# design.net
KiCad netlist of a schematic drawn in Altium Designer
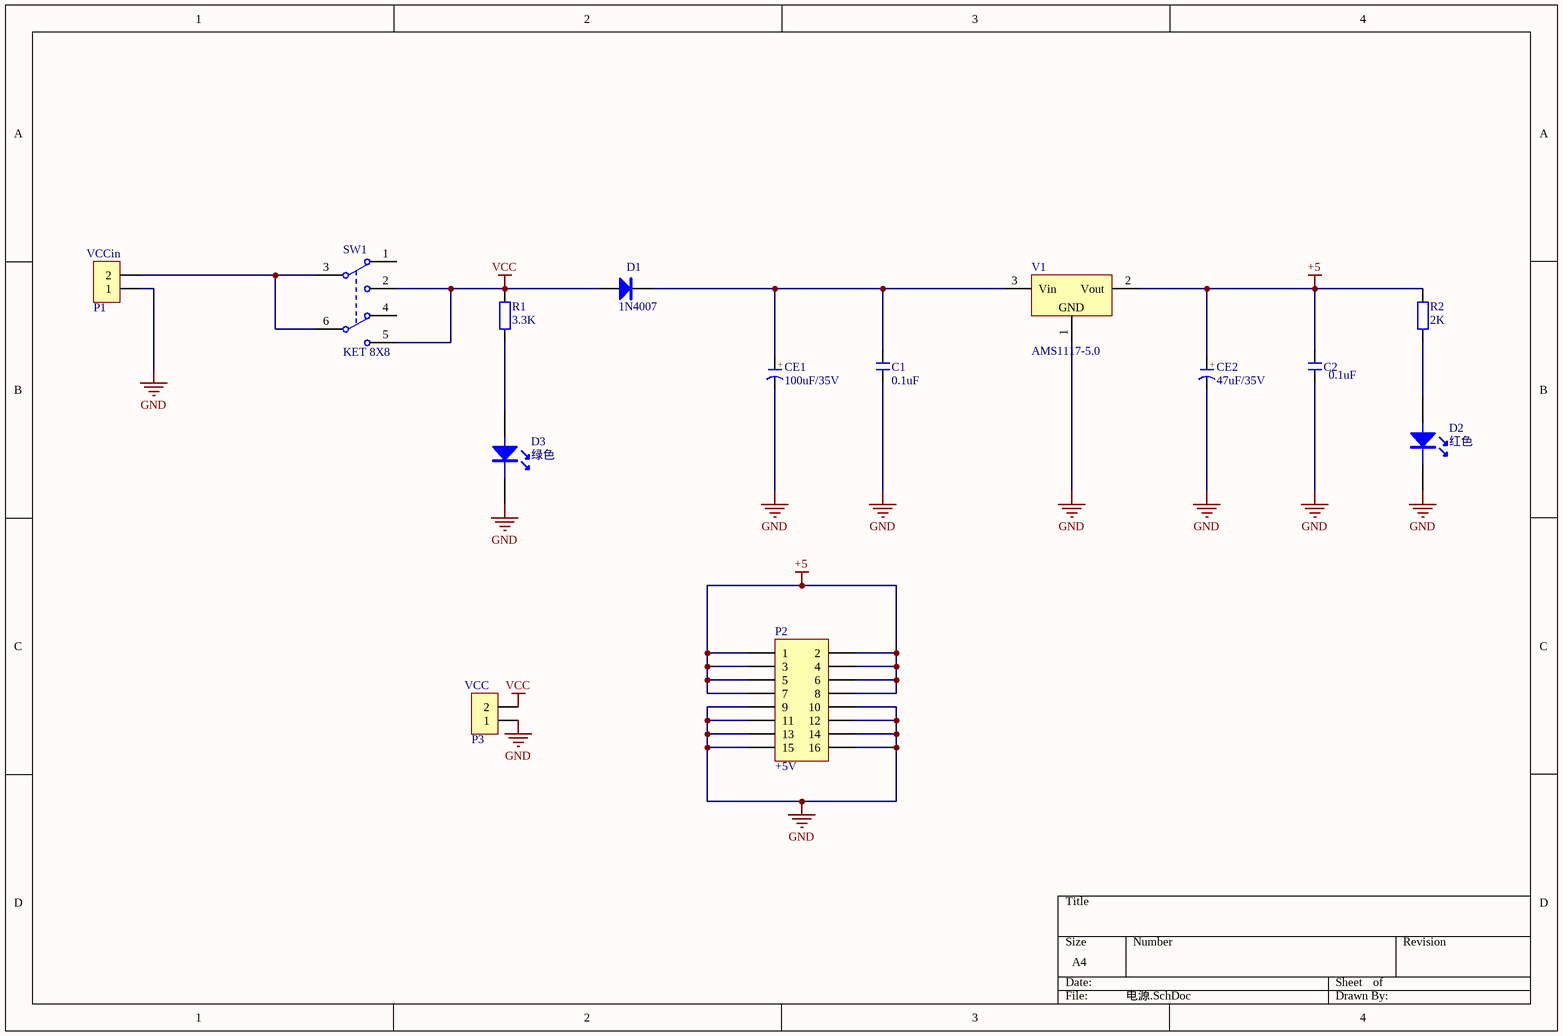
[diagram p0: 电源.SchDoc]

(export (version "E")
  (design (tool "Eeschema 10.0.6"))
  (components
    (comp (ref "C1")
      (value "0.1uF")
      (footprint "C 0805_L")
      (description "贴片电容")
      (libsource (lib "0.1 - 电阻-电容-电感") (part "C"))
    )
    (comp (ref "C2")
      (value "0.1uF")
      (footprint "C 0805_L")
      (description "贴片电容")
      (libsource (lib "0.1 - 电阻-电容-电感") (part "C"))
    )
    (comp (ref "CE1")
      (value "100uF/35V")
      (footprint "RAD0.1")
      (description "直插电解电容")
      (libsource (lib "0.1 - 电阻-电容-电感") (part "CE"))
    )
    (comp (ref "CE2")
      (value "47uF/35V")
      (footprint "RAD0.1")
      (description "直插电解电容")
      (libsource (lib "0.1 - 电阻-电容-电感") (part "CE"))
    )
    (comp (ref "D1")
      (value "1N4007")
      (footprint "SOD-123")
      (description "整流二极管")
      (libsource (lib "0.2 - 二极管-整流桥") (part "1N4007"))
    )
    (comp (ref "D2")
      (value "红色")
      (footprint "LED 1206R")
      (description "LED")
      (libsource (lib "0.2 - 二极管-整流桥") (part "发光二极管"))
    )
    (comp (ref "D3")
      (value "绿色")
      (footprint "LED 1206G")
      (description "LED")
      (libsource (lib "0.2 - 二极管-整流桥") (part "发光二极管"))
    )
    (comp (ref "P1")
      (value "HDR-1X2")
      (footprint "MX 1.25-WI-2P")
      (description "2P接插件")
      (fields (field (name "版权归属") "封装库来自淘宝 ID：黄晶宝石"))
      (libsource (lib "5.0 - 接插件-脚距1.25") (part "Header 2"))
    )
    (comp (ref "P2")
      (value "+5V")
      (footprint "HDR2X8")
      (description "Header, 8-Pin, Dual row")
      (fields (field (name "PUBLISHER") "Altium Limited"))
      (libsource (lib "Miscellaneous Connectors") (part "Header 8X2"))
    )
    (comp (ref "P3")
      (value "HDR-1X2")
      (footprint "MX 1.25-WI-2P")
      (description "2P接插件")
      (fields (field (name "版权归属") "封装库来自淘宝 ID：黄晶宝石"))
      (libsource (lib "5.0 - 接插件-脚距1.25") (part "Header 2"))
    )
    (comp (ref "R1")
      (value "3.3K")
      (footprint "R 0805_L")
      (description "贴片电阻")
      (fields (field (name "版权归属") "来自淘宝 ID：黄晶宝石"))
      (libsource (lib "0.1 - 电阻-电容-电感") (part "R"))
    )
    (comp (ref "R2")
      (value "2K")
      (footprint "R 0201_L")
      (description "贴片电阻")
      (fields (field (name "版权归属") "来自淘宝 ID：黄晶宝石"))
      (libsource (lib "0.1 - 电阻-电容-电感") (part "R"))
    )
    (comp (ref "SW1")
      (value "KET 8X8")
      (footprint "KFT DIP-8X8")
      (description "8*8自锁开关")
      (fields (field (name "版权归属") "封装库来自淘宝 ID：黄晶宝石"))
      (libsource (lib "0.7 - 常用按键-开关") (part "KET 8X8"))
    )
    (comp (ref "V1")
      (value "AMS1117-5.0")
      (footprint "SOT223_L")
      (description "三端稳压芯片")
      (libsource (lib "1.1 - 电源类芯片") (part "AMS1117"))
    )
  )
  (nets
    (net (code "1") (name "+5") (class "Default")
      (node (ref "C2") (pin "2") (pinfunction "2_2") (pintype "passive"))
      (node (ref "CE2") (pin "1") (pinfunction "A_1") (pintype "passive"))
      (node (ref "P2") (pin "1") (pinfunction "1_1") (pintype "passive"))
      (node (ref "P2") (pin "2") (pinfunction "2_2") (pintype "passive"))
      (node (ref "P2") (pin "3") (pinfunction "3_3") (pintype "passive"))
      (node (ref "P2") (pin "4") (pinfunction "4_4") (pintype "passive"))
      (node (ref "P2") (pin "5") (pinfunction "5_5") (pintype "passive"))
      (node (ref "P2") (pin "6") (pinfunction "6_6") (pintype "passive"))
      (node (ref "P2") (pin "7") (pinfunction "7_7") (pintype "passive"))
      (node (ref "P2") (pin "8") (pinfunction "8_8") (pintype "passive"))
      (node (ref "R2") (pin "2") (pinfunction "2_2") (pintype "passive"))
      (node (ref "V1") (pin "2") (pinfunction "Vout_2") (pintype "passive"))
    )
    (net (code "2") (name "GND") (class "Default")
      (node (ref "C1") (pin "1") (pinfunction "1_1") (pintype "passive"))
      (node (ref "C2") (pin "1") (pinfunction "1_1") (pintype "passive"))
      (node (ref "CE1") (pin "2") (pinfunction "K_2") (pintype "passive"))
      (node (ref "CE2") (pin "2") (pinfunction "K_2") (pintype "passive"))
      (node (ref "D2") (pin "K") (pinfunction "2_K") (pintype "passive"))
      (node (ref "D3") (pin "K") (pinfunction "2_K") (pintype "passive"))
      (node (ref "P1") (pin "1") (pinfunction "1_1") (pintype "passive"))
      (node (ref "P2") (pin "10") (pinfunction "10_10") (pintype "passive"))
      (node (ref "P2") (pin "11") (pinfunction "11_11") (pintype "passive"))
      (node (ref "P2") (pin "12") (pinfunction "12_12") (pintype "passive"))
      (node (ref "P2") (pin "13") (pinfunction "13_13") (pintype "passive"))
      (node (ref "P2") (pin "14") (pinfunction "14_14") (pintype "passive"))
      (node (ref "P2") (pin "15") (pinfunction "15_15") (pintype "passive"))
      (node (ref "P2") (pin "16") (pinfunction "16_16") (pintype "passive"))
      (node (ref "P2") (pin "9") (pinfunction "9_9") (pintype "passive"))
      (node (ref "P3") (pin "1") (pinfunction "1_1") (pintype "passive"))
      (node (ref "V1") (pin "1") (pinfunction "GND_1") (pintype "passive"))
    )
    (net (code "3") (name "Net-(CE1-A)") (class "Default")
      (node (ref "C1") (pin "2") (pinfunction "2_2") (pintype "passive"))
      (node (ref "CE1") (pin "1") (pinfunction "A_1") (pintype "passive"))
      (node (ref "D1") (pin "2") (pinfunction "K_2") (pintype "passive"))
      (node (ref "V1") (pin "3") (pinfunction "Vin_3") (pintype "passive"))
    )
    (net (code "4") (name "Net-(D2-1)") (class "Default")
      (node (ref "D2") (pin "A") (pinfunction "1_A") (pintype "passive"))
      (node (ref "R2") (pin "1") (pinfunction "1_1") (pintype "passive"))
    )
    (net (code "5") (name "Net-(D3-1)") (class "Default")
      (node (ref "D3") (pin "A") (pinfunction "1_A") (pintype "passive"))
      (node (ref "R1") (pin "1") (pinfunction "1_1") (pintype "passive"))
    )
    (net (code "6") (name "Net-(SW1-NC2)") (class "Default")
      (node (ref "P1") (pin "2") (pinfunction "2_2") (pintype "passive"))
      (node (ref "SW1") (pin "3") (pinfunction "NO1_3") (pintype "passive"))
      (node (ref "SW1") (pin "6") (pinfunction "NC2_6") (pintype "passive"))
    )
    (net (code "7") (name "VCC") (class "Default")
      (node (ref "D1") (pin "1") (pinfunction "A_1") (pintype "passive"))
      (node (ref "P3") (pin "2") (pinfunction "2_2") (pintype "passive"))
      (node (ref "R1") (pin "2") (pinfunction "2_2") (pintype "passive"))
      (node (ref "SW1") (pin "2") (pinfunction "COM2_2") (pintype "passive"))
      (node (ref "SW1") (pin "5") (pinfunction "COM2_5") (pintype "passive"))
    )
    (net (code "8") (name "unconnected-(SW1-NC1-Pad1)") (class "Default")
      (node (ref "SW1") (pin "1") (pinfunction "NC1_1") (pintype "passive"))
    )
    (net (code "9") (name "unconnected-(SW1-NO2-Pad4)") (class "Default")
      (node (ref "SW1") (pin "4") (pinfunction "NO2_4") (pintype "passive"))
    )
  )
)
